# proj1.net
KiCad netlist of a schematic drawn in EAGLE
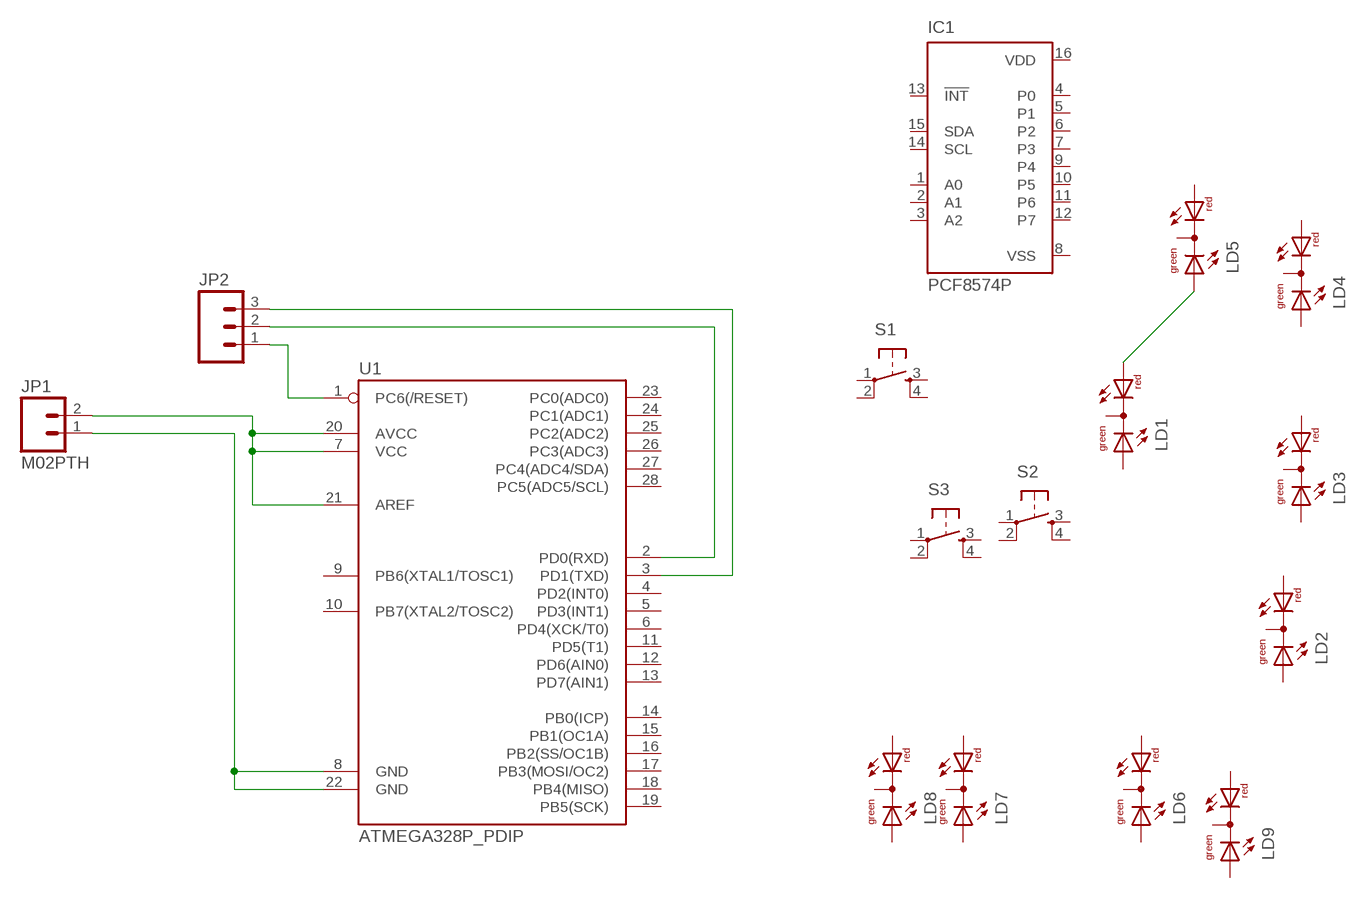
[diagram p0: schematic, sheet 1]

(export (version "E")
  (design (tool "Eeschema 10.0.6"))
  (components
    (comp (ref "IC1")
      (value "PCF8574P")
      (footprint "eagle-import:DIL16")
      (fields (field (name "MPN") "PCF8574PN"))
      (libsource (lib "eagle-import") (part "PCF8574P"))
    )
    (comp (ref "JP1")
      (value "M02PTH")
      (footprint "eagle-import:1X02")
      (libsource (lib "eagle-import") (part "M02PTH"))
    )
    (comp (ref "JP2")
      (value "M03PTH")
      (footprint "eagle-import:1X03")
      (libsource (lib "eagle-import") (part "M03PTH"))
    )
    (comp (ref "LD1")
      (value "DUOLED-RG-C")
      (footprint "eagle-import:DUOLED-C-5MM")
      (libsource (lib "eagle-import") (part "DUOLED-RG-C"))
    )
    (comp (ref "LD2")
      (value "DUOLED-RG-C")
      (footprint "eagle-import:DUOLED-C-5MM")
      (libsource (lib "eagle-import") (part "DUOLED-RG-C"))
    )
    (comp (ref "LD3")
      (value "DUOLED-RG-C")
      (footprint "eagle-import:DUOLED-C-5MM")
      (libsource (lib "eagle-import") (part "DUOLED-RG-C"))
    )
    (comp (ref "LD4")
      (value "DUOLED-RG-C")
      (footprint "eagle-import:DUOLED-C-5MM")
      (libsource (lib "eagle-import") (part "DUOLED-RG-C"))
    )
    (comp (ref "LD5")
      (value "DUOLED-RG-C")
      (footprint "eagle-import:DUOLED-C-5MM")
      (libsource (lib "eagle-import") (part "DUOLED-RG-C"))
    )
    (comp (ref "LD6")
      (value "DUOLED-RG-C")
      (footprint "eagle-import:DUOLED-C-5MM")
      (libsource (lib "eagle-import") (part "DUOLED-RG-C"))
    )
    (comp (ref "LD7")
      (value "DUOLED-RG-C")
      (footprint "eagle-import:DUOLED-C-5MM")
      (libsource (lib "eagle-import") (part "DUOLED-RG-C"))
    )
    (comp (ref "LD8")
      (value "DUOLED-RG-C")
      (footprint "eagle-import:DUOLED-C-5MM")
      (libsource (lib "eagle-import") (part "DUOLED-RG-C"))
    )
    (comp (ref "LD9")
      (value "DUOLED-RG-C")
      (footprint "eagle-import:DUOLED-C-5MM")
      (libsource (lib "eagle-import") (part "DUOLED-RG-C"))
    )
    (comp (ref "S1")
      (value "TAC_SWITCHPTH")
      (footprint "eagle-import:TACTILE-PTH")
      (libsource (lib "eagle-import") (part "TAC_SWITCHPTH"))
    )
    (comp (ref "S2")
      (value "TAC_SWITCHPTH")
      (footprint "eagle-import:TACTILE-PTH")
      (libsource (lib "eagle-import") (part "TAC_SWITCHPTH"))
    )
    (comp (ref "S3")
      (value "TAC_SWITCHPTH")
      (footprint "eagle-import:TACTILE-PTH")
      (libsource (lib "eagle-import") (part "TAC_SWITCHPTH"))
    )
    (comp (ref "U1")
      (value "ATMEGA328P_PDIP")
      (footprint "eagle-import:DIL28-3")
      (libsource (lib "eagle-import") (part "ATMEGA328P_PDIP"))
    )
  )
  (nets
    (net (code "1") (name "/VDD") (class "Default")
      (node (ref "IC1") (pin "16") (pinfunction "VDD_16") (pintype "power_in"))
    )
    (net (code "2") (name "/VSS") (class "Default")
      (node (ref "IC1") (pin "8") (pinfunction "VSS_8") (pintype "power_in"))
    )
    (net (code "3") (name "Net-(JP1-Pad1)") (class "Default")
      (node (ref "JP1") (pin "1") (pinfunction "1_1") (pintype "passive"))
      (node (ref "U1") (pin "22") (pinfunction "GND_22") (pintype "bidirectional"))
      (node (ref "U1") (pin "8") (pinfunction "GND_8") (pintype "bidirectional"))
    )
    (net (code "4") (name "Net-(LD5-AG)") (class "Default")
      (node (ref "LD1") (pin "AR") (pinfunction "AR_AR") (pintype "passive"))
      (node (ref "LD5") (pin "AX") (pinfunction "AG_AX") (pintype "passive"))
    )
    (net (code "5") (name "Net-(U1-AREF)") (class "Default")
      (node (ref "JP1") (pin "2") (pinfunction "2_2") (pintype "passive"))
      (node (ref "U1") (pin "20") (pinfunction "AVCC_20") (pintype "bidirectional"))
      (node (ref "U1") (pin "21") (pinfunction "AREF_21") (pintype "bidirectional"))
      (node (ref "U1") (pin "7") (pinfunction "VCC_7") (pintype "bidirectional"))
    )
    (net (code "6") (name "Net-(U1-PC6({slash}RESET))") (class "Default")
      (node (ref "JP2") (pin "1") (pinfunction "1_1") (pintype "passive"))
      (node (ref "U1") (pin "1") (pinfunction "PC6(/RESET)_1") (pintype "bidirectional"))
    )
    (net (code "7") (name "Net-(U1-PD0(RXD))") (class "Default")
      (node (ref "JP2") (pin "2") (pinfunction "2_2") (pintype "passive"))
      (node (ref "U1") (pin "2") (pinfunction "PD0(RXD)_2") (pintype "bidirectional"))
    )
    (net (code "8") (name "Net-(U1-PD1(TXD))") (class "Default")
      (node (ref "JP2") (pin "3") (pinfunction "3_3") (pintype "passive"))
      (node (ref "U1") (pin "3") (pinfunction "PD1(TXD)_3") (pintype "bidirectional"))
    )
    (net (code "9") (name "unconnected-(IC1-A0-Pad1)") (class "Default")
      (node (ref "IC1") (pin "1") (pinfunction "A0_1") (pintype "input"))
    )
    (net (code "10") (name "unconnected-(IC1-A1-Pad2)") (class "Default")
      (node (ref "IC1") (pin "2") (pinfunction "A1_2") (pintype "input"))
    )
    (net (code "11") (name "unconnected-(IC1-A2-Pad3)") (class "Default")
      (node (ref "IC1") (pin "3") (pinfunction "A2_3") (pintype "input"))
    )
    (net (code "12") (name "unconnected-(IC1-P0-Pad4)") (class "Default")
      (node (ref "IC1") (pin "4") (pinfunction "P0_4") (pintype "bidirectional"))
    )
    (net (code "13") (name "unconnected-(IC1-P1-Pad5)") (class "Default")
      (node (ref "IC1") (pin "5") (pinfunction "P1_5") (pintype "bidirectional"))
    )
    (net (code "14") (name "unconnected-(IC1-P2-Pad6)") (class "Default")
      (node (ref "IC1") (pin "6") (pinfunction "P2_6") (pintype "bidirectional"))
    )
    (net (code "15") (name "unconnected-(IC1-P3-Pad7)") (class "Default")
      (node (ref "IC1") (pin "7") (pinfunction "P3_7") (pintype "bidirectional"))
    )
    (net (code "16") (name "unconnected-(IC1-P4-Pad9)") (class "Default")
      (node (ref "IC1") (pin "9") (pinfunction "P4_9") (pintype "bidirectional"))
    )
    (net (code "17") (name "unconnected-(IC1-P5-Pad10)") (class "Default")
      (node (ref "IC1") (pin "10") (pinfunction "P5_10") (pintype "bidirectional"))
    )
    (net (code "18") (name "unconnected-(IC1-P6-Pad11)") (class "Default")
      (node (ref "IC1") (pin "11") (pinfunction "P6_11") (pintype "bidirectional"))
    )
    (net (code "19") (name "unconnected-(IC1-P7-Pad12)") (class "Default")
      (node (ref "IC1") (pin "12") (pinfunction "P7_12") (pintype "bidirectional"))
    )
    (net (code "20") (name "unconnected-(IC1-SCL-Pad14)") (class "Default")
      (node (ref "IC1") (pin "14") (pinfunction "SCL_14") (pintype "input"))
    )
    (net (code "21") (name "unconnected-(IC1-SDA-Pad15)") (class "Default")
      (node (ref "IC1") (pin "15") (pinfunction "SDA_15") (pintype "bidirectional"))
    )
    (net (code "22") (name "unconnected-(IC1-~{INT}-Pad13)") (class "Default")
      (node (ref "IC1") (pin "13") (pinfunction "~{INT}_13") (pintype "output"))
    )
    (net (code "23") (name "unconnected-(LD1-AG-PadAX)") (class "Default")
      (node (ref "LD1") (pin "AX") (pinfunction "AG_AX") (pintype "passive"))
    )
    (net (code "24") (name "unconnected-(LD1-PadC)") (class "Default")
      (node (ref "LD1") (pin "C") (pinfunction "C_C") (pintype "passive"))
    )
    (net (code "25") (name "unconnected-(LD2-AG-PadAX)") (class "Default")
      (node (ref "LD2") (pin "AX") (pinfunction "AG_AX") (pintype "passive"))
    )
    (net (code "26") (name "unconnected-(LD2-PadAR)") (class "Default")
      (node (ref "LD2") (pin "AR") (pinfunction "AR_AR") (pintype "passive"))
    )
    (net (code "27") (name "unconnected-(LD2-PadC)") (class "Default")
      (node (ref "LD2") (pin "C") (pinfunction "C_C") (pintype "passive"))
    )
    (net (code "28") (name "unconnected-(LD3-AG-PadAX)") (class "Default")
      (node (ref "LD3") (pin "AX") (pinfunction "AG_AX") (pintype "passive"))
    )
    (net (code "29") (name "unconnected-(LD3-PadAR)") (class "Default")
      (node (ref "LD3") (pin "AR") (pinfunction "AR_AR") (pintype "passive"))
    )
    (net (code "30") (name "unconnected-(LD3-PadC)") (class "Default")
      (node (ref "LD3") (pin "C") (pinfunction "C_C") (pintype "passive"))
    )
    (net (code "31") (name "unconnected-(LD4-AG-PadAX)") (class "Default")
      (node (ref "LD4") (pin "AX") (pinfunction "AG_AX") (pintype "passive"))
    )
    (net (code "32") (name "unconnected-(LD4-PadAR)") (class "Default")
      (node (ref "LD4") (pin "AR") (pinfunction "AR_AR") (pintype "passive"))
    )
    (net (code "33") (name "unconnected-(LD4-PadC)") (class "Default")
      (node (ref "LD4") (pin "C") (pinfunction "C_C") (pintype "passive"))
    )
    (net (code "34") (name "unconnected-(LD5-PadAR)") (class "Default")
      (node (ref "LD5") (pin "AR") (pinfunction "AR_AR") (pintype "passive"))
    )
    (net (code "35") (name "unconnected-(LD5-PadC)") (class "Default")
      (node (ref "LD5") (pin "C") (pinfunction "C_C") (pintype "passive"))
    )
    (net (code "36") (name "unconnected-(LD6-AG-PadAX)") (class "Default")
      (node (ref "LD6") (pin "AX") (pinfunction "AG_AX") (pintype "passive"))
    )
    (net (code "37") (name "unconnected-(LD6-PadAR)") (class "Default")
      (node (ref "LD6") (pin "AR") (pinfunction "AR_AR") (pintype "passive"))
    )
    (net (code "38") (name "unconnected-(LD6-PadC)") (class "Default")
      (node (ref "LD6") (pin "C") (pinfunction "C_C") (pintype "passive"))
    )
    (net (code "39") (name "unconnected-(LD7-AG-PadAX)") (class "Default")
      (node (ref "LD7") (pin "AX") (pinfunction "AG_AX") (pintype "passive"))
    )
    (net (code "40") (name "unconnected-(LD7-PadAR)") (class "Default")
      (node (ref "LD7") (pin "AR") (pinfunction "AR_AR") (pintype "passive"))
    )
    (net (code "41") (name "unconnected-(LD7-PadC)") (class "Default")
      (node (ref "LD7") (pin "C") (pinfunction "C_C") (pintype "passive"))
    )
    (net (code "42") (name "unconnected-(LD8-AG-PadAX)") (class "Default")
      (node (ref "LD8") (pin "AX") (pinfunction "AG_AX") (pintype "passive"))
    )
    (net (code "43") (name "unconnected-(LD8-PadAR)") (class "Default")
      (node (ref "LD8") (pin "AR") (pinfunction "AR_AR") (pintype "passive"))
    )
    (net (code "44") (name "unconnected-(LD8-PadC)") (class "Default")
      (node (ref "LD8") (pin "C") (pinfunction "C_C") (pintype "passive"))
    )
    (net (code "45") (name "unconnected-(LD9-AG-PadAX)") (class "Default")
      (node (ref "LD9") (pin "AX") (pinfunction "AG_AX") (pintype "passive"))
    )
    (net (code "46") (name "unconnected-(LD9-PadAR)") (class "Default")
      (node (ref "LD9") (pin "AR") (pinfunction "AR_AR") (pintype "passive"))
    )
    (net (code "47") (name "unconnected-(LD9-PadC)") (class "Default")
      (node (ref "LD9") (pin "C") (pinfunction "C_C") (pintype "passive"))
    )
    (net (code "48") (name "unconnected-(S1-Pad1)") (class "Default")
      (node (ref "S1") (pin "1") (pinfunction "1_1") (pintype "passive"))
    )
    (net (code "49") (name "unconnected-(S1-Pad2)") (class "Default")
      (node (ref "S1") (pin "2") (pinfunction "2_2") (pintype "passive"))
    )
    (net (code "50") (name "unconnected-(S1-Pad3)") (class "Default")
      (node (ref "S1") (pin "3") (pinfunction "3_3") (pintype "passive"))
    )
    (net (code "51") (name "unconnected-(S1-Pad4)") (class "Default")
      (node (ref "S1") (pin "4") (pinfunction "4_4") (pintype "passive"))
    )
    (net (code "52") (name "unconnected-(S2-Pad1)") (class "Default")
      (node (ref "S2") (pin "1") (pinfunction "1_1") (pintype "passive"))
    )
    (net (code "53") (name "unconnected-(S2-Pad2)") (class "Default")
      (node (ref "S2") (pin "2") (pinfunction "2_2") (pintype "passive"))
    )
    (net (code "54") (name "unconnected-(S2-Pad3)") (class "Default")
      (node (ref "S2") (pin "3") (pinfunction "3_3") (pintype "passive"))
    )
    (net (code "55") (name "unconnected-(S2-Pad4)") (class "Default")
      (node (ref "S2") (pin "4") (pinfunction "4_4") (pintype "passive"))
    )
    (net (code "56") (name "unconnected-(S3-Pad1)") (class "Default")
      (node (ref "S3") (pin "1") (pinfunction "1_1") (pintype "passive"))
    )
    (net (code "57") (name "unconnected-(S3-Pad2)") (class "Default")
      (node (ref "S3") (pin "2") (pinfunction "2_2") (pintype "passive"))
    )
    (net (code "58") (name "unconnected-(S3-Pad3)") (class "Default")
      (node (ref "S3") (pin "3") (pinfunction "3_3") (pintype "passive"))
    )
    (net (code "59") (name "unconnected-(S3-Pad4)") (class "Default")
      (node (ref "S3") (pin "4") (pinfunction "4_4") (pintype "passive"))
    )
    (net (code "60") (name "unconnected-(U1-PB0(ICP)-Pad14)") (class "Default")
      (node (ref "U1") (pin "14") (pinfunction "PB0(ICP)_14") (pintype "bidirectional"))
    )
    (net (code "61") (name "unconnected-(U1-PB1(OC1A)-Pad15)") (class "Default")
      (node (ref "U1") (pin "15") (pinfunction "PB1(OC1A)_15") (pintype "bidirectional"))
    )
    (net (code "62") (name "unconnected-(U1-PB2(SS{slash}OC1B)-Pad16)") (class "Default")
      (node (ref "U1") (pin "16") (pinfunction "PB2(SS/OC1B)_16") (pintype "bidirectional"))
    )
    (net (code "63") (name "unconnected-(U1-PB3(MOSI{slash}OC2)-Pad17)") (class "Default")
      (node (ref "U1") (pin "17") (pinfunction "PB3(MOSI/OC2)_17") (pintype "bidirectional"))
    )
    (net (code "64") (name "unconnected-(U1-PB4(MISO)-Pad18)") (class "Default")
      (node (ref "U1") (pin "18") (pinfunction "PB4(MISO)_18") (pintype "bidirectional"))
    )
    (net (code "65") (name "unconnected-(U1-PB5(SCK)-Pad19)") (class "Default")
      (node (ref "U1") (pin "19") (pinfunction "PB5(SCK)_19") (pintype "bidirectional"))
    )
    (net (code "66") (name "unconnected-(U1-PB6(XTAL1{slash}TOSC1)-Pad9)") (class "Default")
      (node (ref "U1") (pin "9") (pinfunction "PB6(XTAL1/TOSC1)_9") (pintype "bidirectional"))
    )
    (net (code "67") (name "unconnected-(U1-PB7(XTAL2{slash}TOSC2)-Pad10)") (class "Default")
      (node (ref "U1") (pin "10") (pinfunction "PB7(XTAL2/TOSC2)_10") (pintype "bidirectional"))
    )
    (net (code "68") (name "unconnected-(U1-PC0(ADC0)-Pad23)") (class "Default")
      (node (ref "U1") (pin "23") (pinfunction "PC0(ADC0)_23") (pintype "bidirectional"))
    )
    (net (code "69") (name "unconnected-(U1-PC1(ADC1)-Pad24)") (class "Default")
      (node (ref "U1") (pin "24") (pinfunction "PC1(ADC1)_24") (pintype "bidirectional"))
    )
    (net (code "70") (name "unconnected-(U1-PC2(ADC2)-Pad25)") (class "Default")
      (node (ref "U1") (pin "25") (pinfunction "PC2(ADC2)_25") (pintype "bidirectional"))
    )
    (net (code "71") (name "unconnected-(U1-PC3(ADC3)-Pad26)") (class "Default")
      (node (ref "U1") (pin "26") (pinfunction "PC3(ADC3)_26") (pintype "bidirectional"))
    )
    (net (code "72") (name "unconnected-(U1-PC4(ADC4{slash}SDA)-Pad27)") (class "Default")
      (node (ref "U1") (pin "27") (pinfunction "PC4(ADC4/SDA)_27") (pintype "bidirectional"))
    )
    (net (code "73") (name "unconnected-(U1-PC5(ADC5{slash}SCL)-Pad28)") (class "Default")
      (node (ref "U1") (pin "28") (pinfunction "PC5(ADC5/SCL)_28") (pintype "bidirectional"))
    )
    (net (code "74") (name "unconnected-(U1-PD2(INT0)-Pad4)") (class "Default")
      (node (ref "U1") (pin "4") (pinfunction "PD2(INT0)_4") (pintype "bidirectional"))
    )
    (net (code "75") (name "unconnected-(U1-PD3(INT1)-Pad5)") (class "Default")
      (node (ref "U1") (pin "5") (pinfunction "PD3(INT1)_5") (pintype "bidirectional"))
    )
    (net (code "76") (name "unconnected-(U1-PD4(XCK{slash}T0)-Pad6)") (class "Default")
      (node (ref "U1") (pin "6") (pinfunction "PD4(XCK/T0)_6") (pintype "bidirectional"))
    )
    (net (code "77") (name "unconnected-(U1-PD5(T1)-Pad11)") (class "Default")
      (node (ref "U1") (pin "11") (pinfunction "PD5(T1)_11") (pintype "bidirectional"))
    )
    (net (code "78") (name "unconnected-(U1-PD6(AIN0)-Pad12)") (class "Default")
      (node (ref "U1") (pin "12") (pinfunction "PD6(AIN0)_12") (pintype "bidirectional"))
    )
    (net (code "79") (name "unconnected-(U1-PD7(AIN1)-Pad13)") (class "Default")
      (node (ref "U1") (pin "13") (pinfunction "PD7(AIN1)_13") (pintype "bidirectional"))
    )
  )
)
